# EasyEDA.net
KiCad netlist of a schematic drawn in EasyEDA
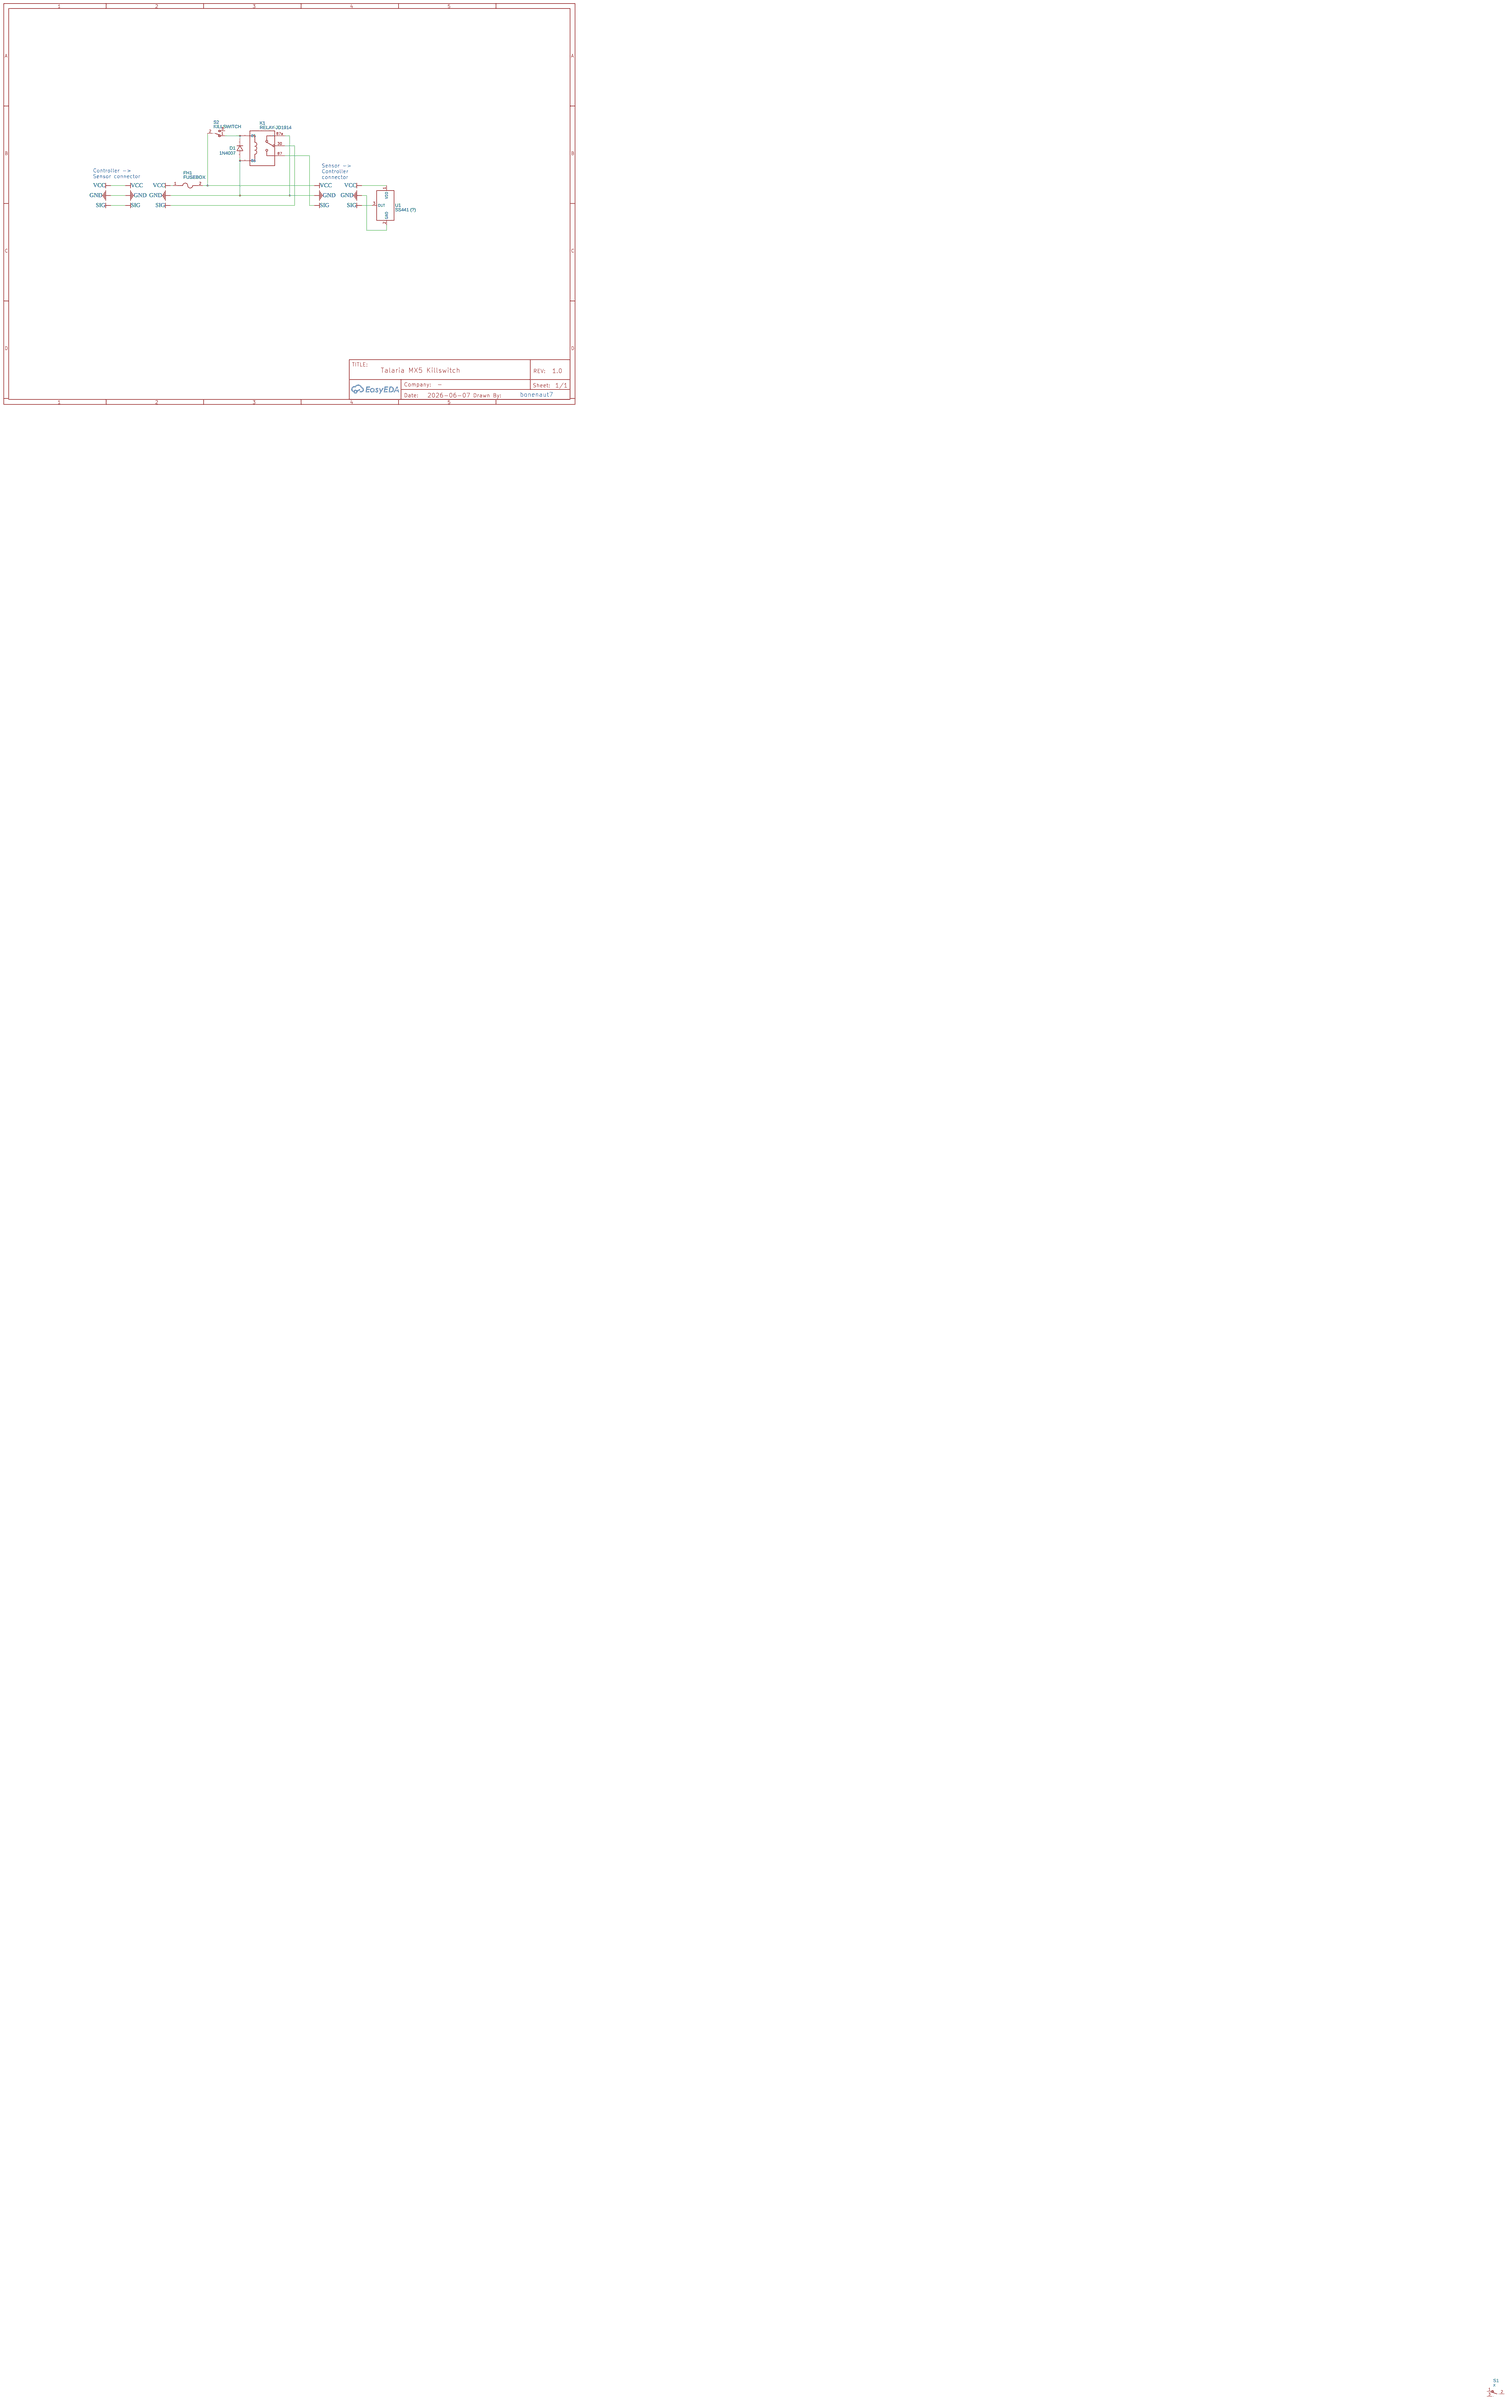
[diagram p0: schematic sheet]

(export (version "E")
  (design (tool "Eeschema 10.0.6"))
  (components
    (comp (ref "D1")
      (value "1N4007")
      (fields (field (name "Manufacturer Part") "1N4007W") (field (name "Manufacturer") "BLUE ROCKET"))
      (libsource (lib "") (part "1N4007W"))
    )
    (comp (ref "FH1")
      (value "FUSEBOX")
      (fields (field (name "Manufacturer Part") "0031.8225") (field (name "Manufacturer") "SCHURTER"))
      (libsource (lib "") (part "0031.8225"))
    )
    (comp (ref "K1")
      (value "RELAY-JD1914")
      (fields (field (name "Manufacturer Part") "SLA-12VDC-SL-C") (field (name "Manufacturer") "SONGLE"))
      (libsource (lib "") (part "RELAY-JD1914"))
    )
    (comp (ref "S1") (value "x") (libsource (lib "") (part "SWITCH-SLIDE-SPDT-200MA-30V")))
    (comp (ref "S2") (value "KILLSWITCH") (libsource (lib "") (part "SWITCH-SLIDE-SPDT-200MA-30V_1")))
    (comp (ref "U1")
      (value "SS441 (?)")
      (fields
        (field (name "Manufacturer Part") "US5881KUA-AAA-000-SP")
        (field (name "Manufacturer") "Melexis(比利时迈来芯)")
      )
      (libsource (lib "") (part "US5881KUA-AAA-000-SP"))
    )
  )
  (nets
    (net (code "1") (name "GND") (class "Default")
      (node (ref "D1") (pin "2") (pinfunction "2_2") (pintype "unspecified"))
      (node (ref "K1") (pin "86") (pinfunction "86_86") (pintype "unspecified"))
      (node (ref "K1") (pin "87a") (pinfunction "87a_87a") (pintype "unspecified"))
      (node (ref "U1") (pin "2") (pinfunction "GND_2") (pintype "unspecified"))
    )
    (net (code "2") (name "Net-(D1-Pad1)") (class "Default")
      (node (ref "D1") (pin "1") (pinfunction "1_1") (pintype "unspecified"))
      (node (ref "K1") (pin "85") (pinfunction "85_85") (pintype "unspecified"))
      (node (ref "S2") (pin "1") (pinfunction "1_1") (pintype "unspecified"))
    )
    (net (code "3") (name "SIG") (class "Default")
      (node (ref "K1") (pin "30") (pinfunction "30_30") (pintype "unspecified"))
      (node (ref "K1") (pin "87") (pinfunction "87_87") (pintype "unspecified"))
      (node (ref "U1") (pin "3") (pinfunction "OUT_3") (pintype "unspecified"))
    )
    (net (code "4") (name "VCC") (class "Default")
      (node (ref "FH1") (pin "1") (pinfunction "1_1") (pintype "unspecified"))
      (node (ref "FH1") (pin "2") (pinfunction "2_2") (pintype "unspecified"))
      (node (ref "S2") (pin "2") (pinfunction "2_2") (pintype "unspecified"))
      (node (ref "U1") (pin "1") (pinfunction "VDD_1") (pintype "unspecified"))
    )
    (net (code "5") (name "unconnected-(S1-Pad1)") (class "Default")
      (node (ref "S1") (pin "1") (pinfunction "1_1") (pintype "unspecified"))
    )
    (net (code "6") (name "unconnected-(S1-Pad2)") (class "Default")
      (node (ref "S1") (pin "2") (pinfunction "2_2") (pintype "unspecified"))
    )
    (net (code "7") (name "unconnected-(S1-Pad3)") (class "Default")
      (node (ref "S1") (pin "3") (pinfunction "3_3") (pintype "unspecified"))
    )
    (net (code "8") (name "unconnected-(S2-Pad3)") (class "Default")
      (node (ref "S2") (pin "3") (pinfunction "3_3") (pintype "unspecified"))
    )
  )
)
